# EEZ_AUX_PS_r5B6a.net
KiCad netlist of a schematic drawn in EAGLE
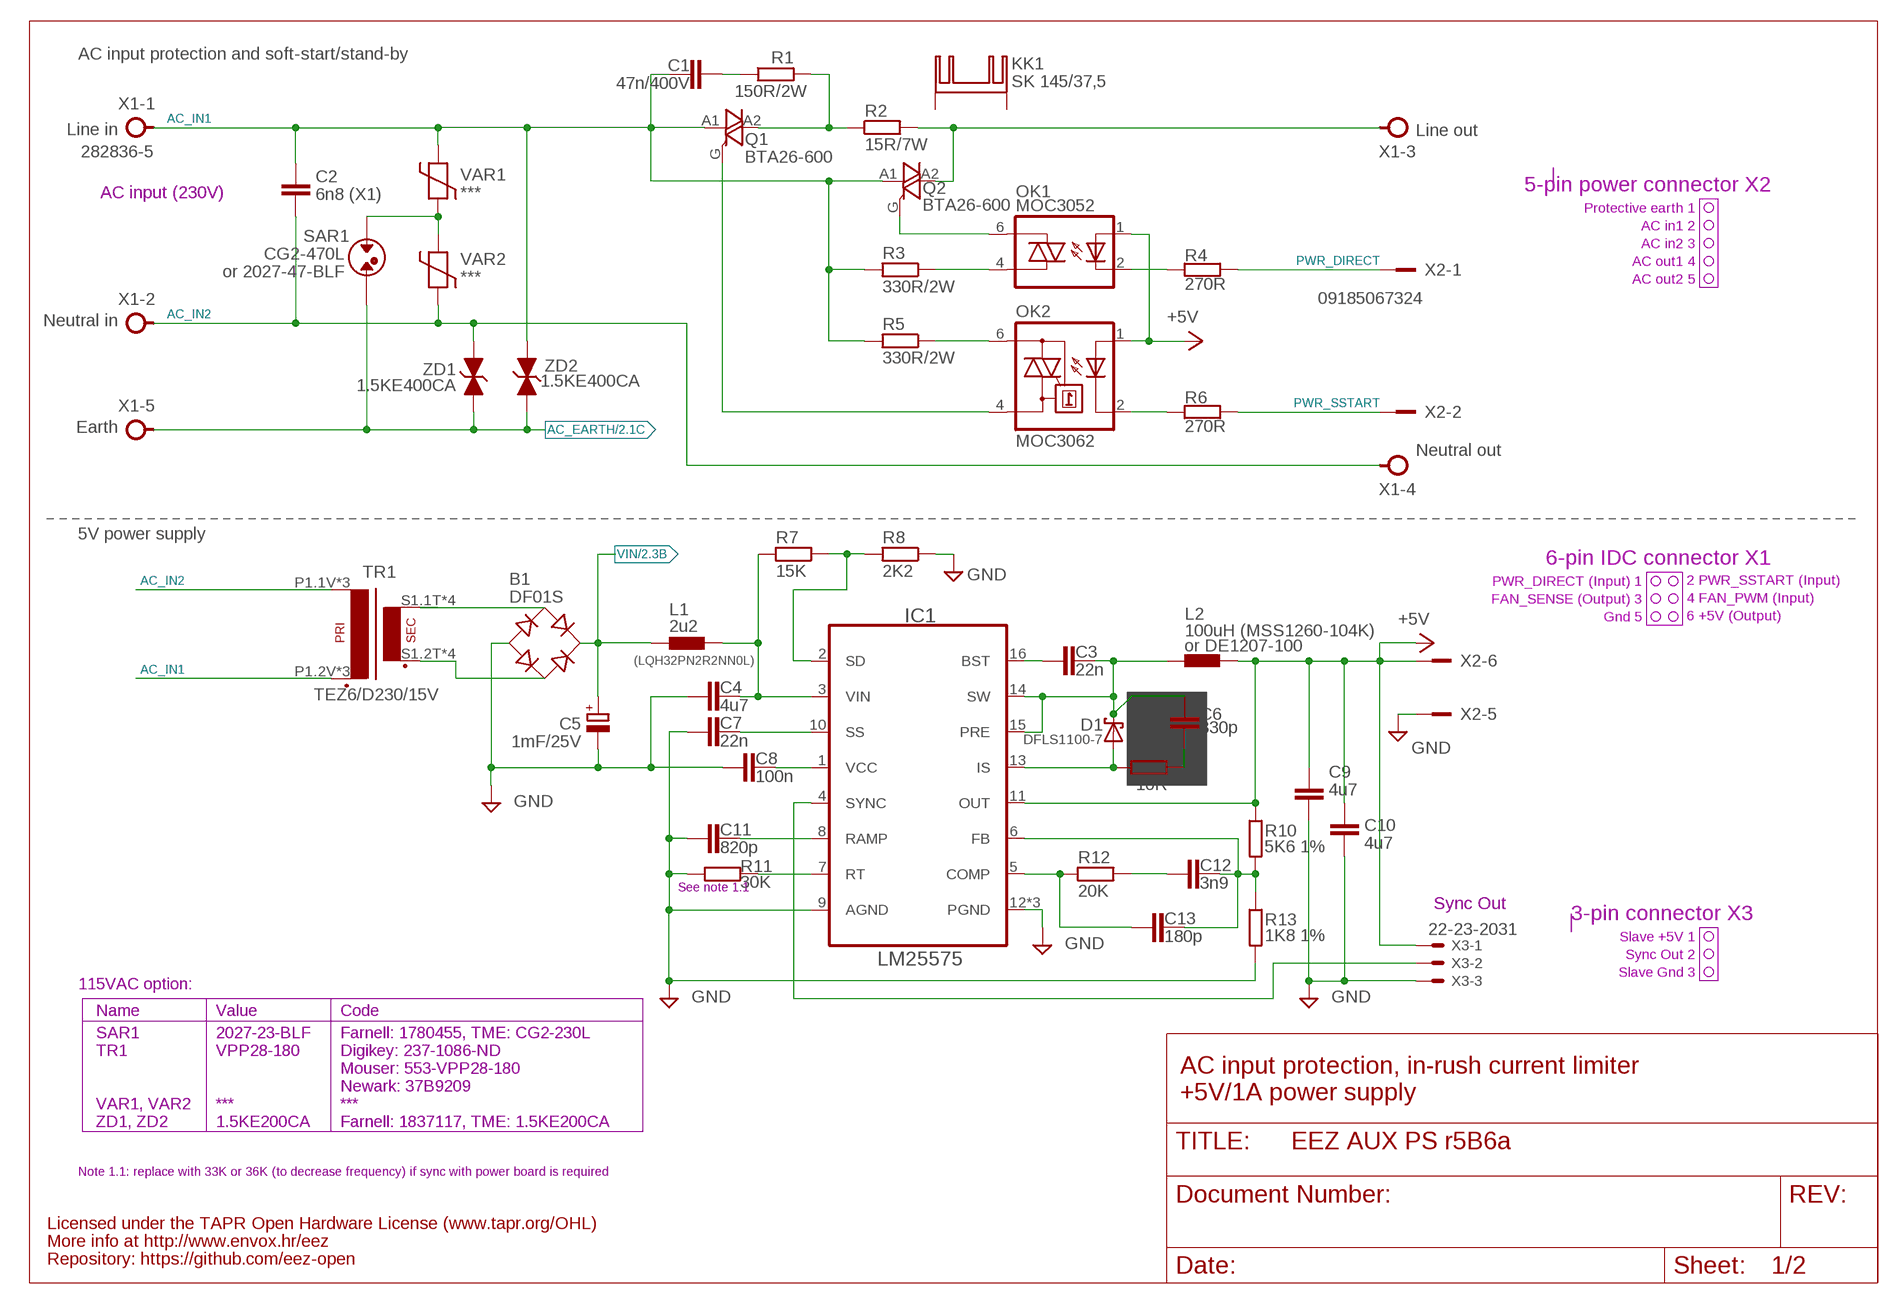
[diagram p0: schematic, sheet 1]
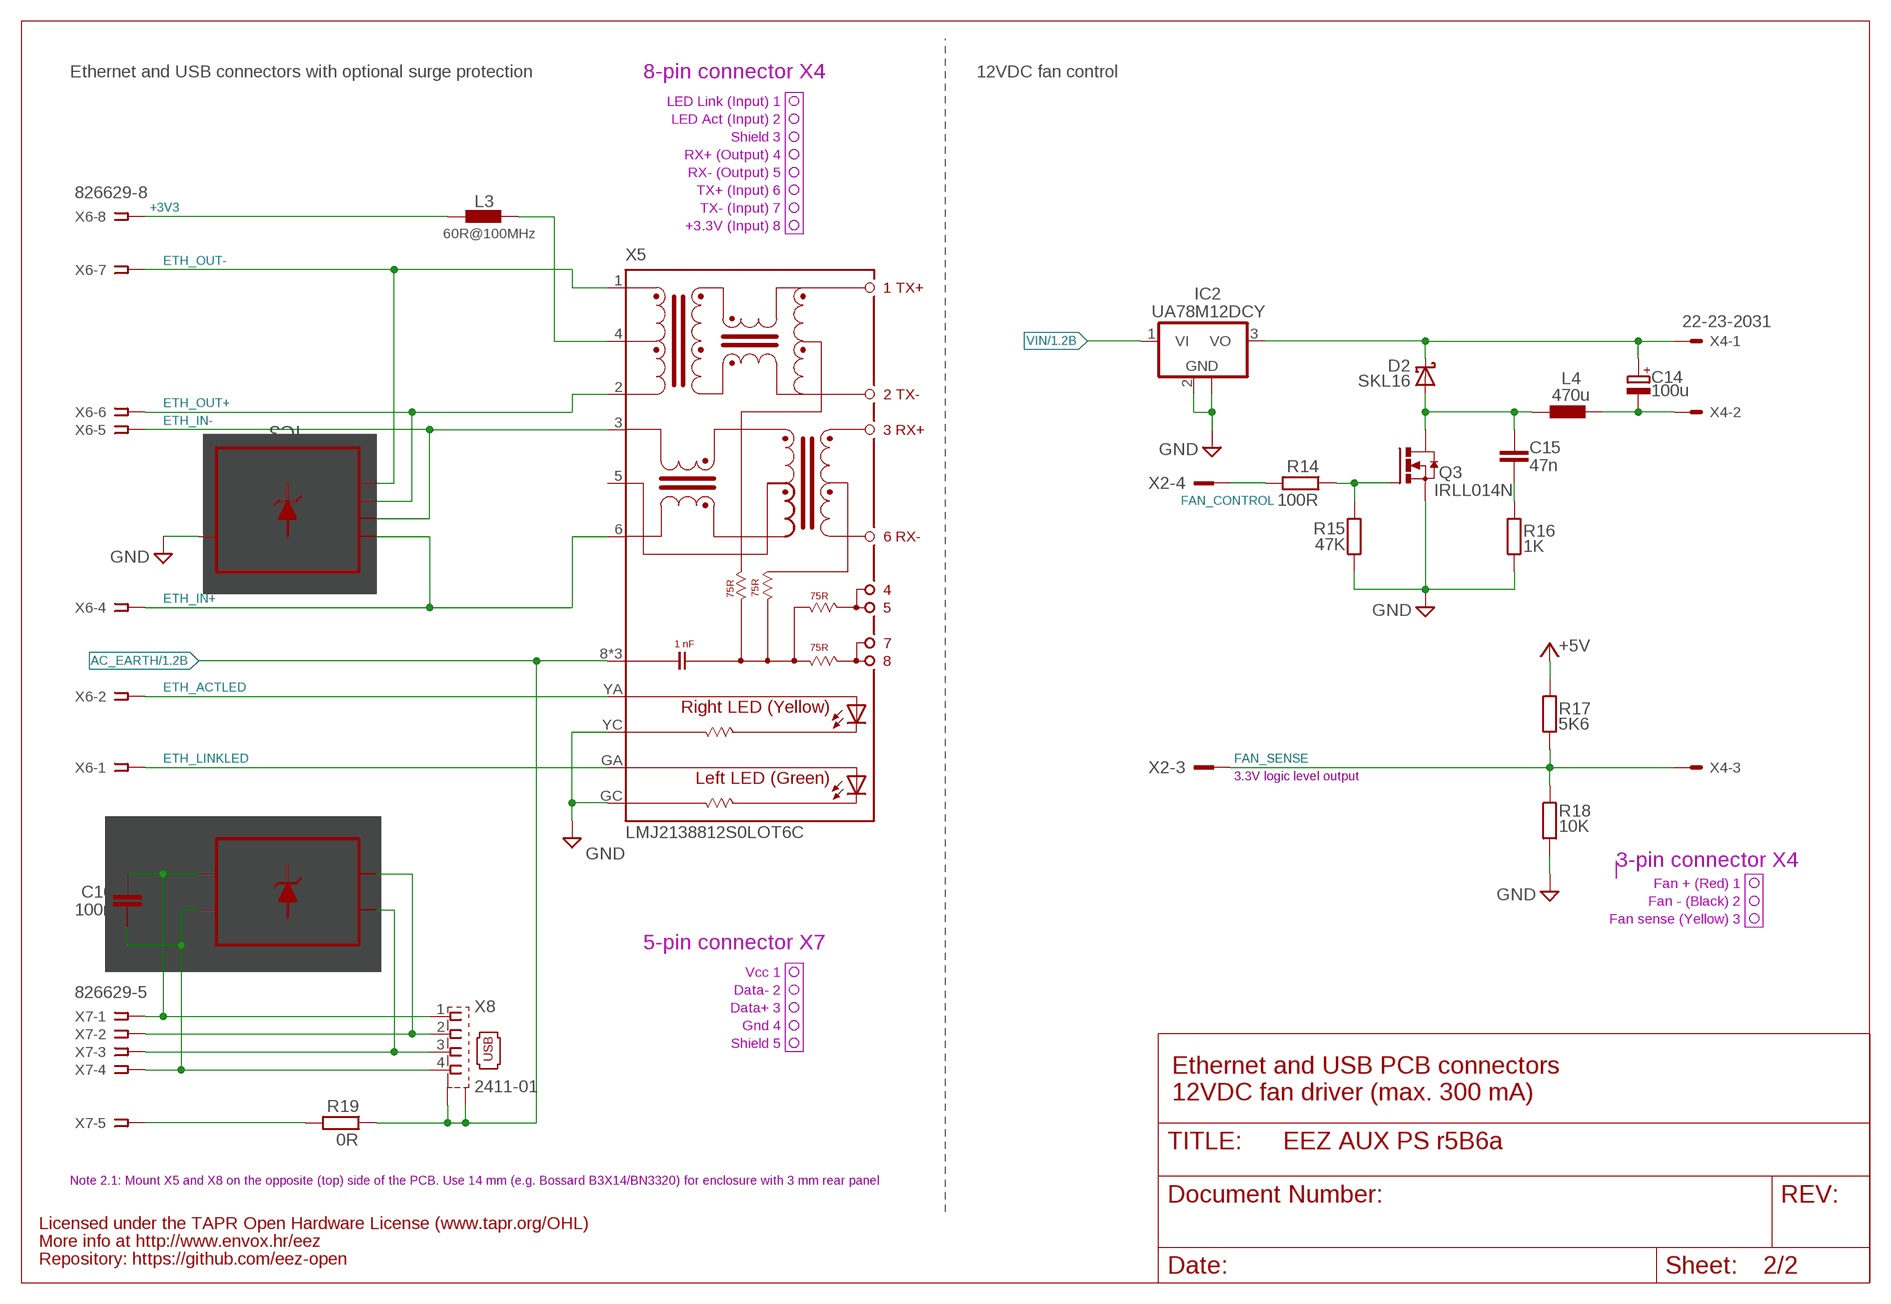
[diagram p1: schematic, sheet 2]

(export (version "E")
  (design (tool "Eeschema 10.0.6"))
  (components
    (comp (ref "B1")
      (value "DF01S")
      (footprint "eagle-import:DFS")
      (libsource (lib "eagle-import") (part "DFS01"))
    )
    (comp (ref "C1")
      (value "47n/400V")
      (footprint "eagle-import:C075-052X106")
      (libsource (lib "eagle-import") (part "C-EU075-052X106"))
    )
    (comp (ref "C2")
      (value "6n8 (X1)")
      (footprint "eagle-import:C102-064X133")
      (libsource (lib "eagle-import") (part "C-EU102-064X133"))
    )
    (comp (ref "C3")
      (value "22n")
      (footprint "eagle-import:C0805")
      (libsource (lib "eagle-import") (part "C-EUC0805"))
    )
    (comp (ref "C4")
      (value "4u7")
      (footprint "eagle-import:C1210")
      (libsource (lib "eagle-import") (part "C-EUC1210"))
    )
    (comp (ref "C5")
      (value "1mF/25V")
      (footprint "eagle-import:ECAP5_10.5")
      (libsource (lib "eagle-import") (part "ECAP5G_10.5MM"))
    )
    (comp (ref "C6")
      (value "330p")
      (footprint "eagle-import:C0805")
      (libsource (lib "eagle-import") (part "C-EUC0805"))
    )
    (comp (ref "C7")
      (value "22n")
      (footprint "eagle-import:C0805")
      (libsource (lib "eagle-import") (part "C-EUC0805"))
    )
    (comp (ref "C8")
      (value "100n")
      (footprint "eagle-import:C0805")
      (libsource (lib "eagle-import") (part "C-EUC0805"))
    )
    (comp (ref "C9")
      (value "4u7")
      (footprint "eagle-import:C1210")
      (libsource (lib "eagle-import") (part "C-EUC1210"))
    )
    (comp (ref "C10")
      (value "4u7")
      (footprint "eagle-import:C1210")
      (libsource (lib "eagle-import") (part "C-EUC1210"))
    )
    (comp (ref "C11")
      (value "820p")
      (footprint "eagle-import:C0805")
      (libsource (lib "eagle-import") (part "C-EUC0805"))
    )
    (comp (ref "C12")
      (value "3n9")
      (footprint "eagle-import:C0805")
      (libsource (lib "eagle-import") (part "C-EUC0805"))
    )
    (comp (ref "C13")
      (value "180p")
      (footprint "eagle-import:C0805")
      (libsource (lib "eagle-import") (part "C-EUC0805"))
    )
    (comp (ref "D1")
      (value "DFLS1100-7")
      (footprint "eagle-import:SOD123")
      (libsource (lib "eagle-import") (part "SCHOTTKYSOD123"))
    )
    (comp (ref "IC1")
      (value "LM25575")
      (footprint "eagle-import:SOP65P640X110-17N_HOLE")
      (libsource (lib "eagle-import") (part "LM(2)5575"))
    )
    (comp (ref "KK1")
      (value "SK 145/37,5")
      (footprint "eagle-import:SK145")
      (libsource (lib "eagle-import") (part "SK145"))
    )
    (comp (ref "L1")
      (value "2u2")
      (footprint "eagle-import:L1210")
      (libsource (lib "eagle-import") (part "L1210"))
    )
    (comp (ref "L2")
      (value "100uH (MSS1260-104K)")
      (footprint "eagle-import:MSS1278")
      (libsource (lib "eagle-import") (part "COILCRAFT_MSS1278"))
    )
    (comp (ref "OK1")
      (value "MOC3052")
      (footprint "eagle-import:DIL6-SMD")
      (libsource (lib "eagle-import") (part "MOC305X"))
    )
    (comp (ref "OK2")
      (value "MOC3062")
      (footprint "eagle-import:DIL6-SMD")
      (fields
        (field (name "MF") "FAIRCHILD SEMICONDUCTOR")
        (field (name "MPN") "MOC3033S-M")
        (field (name "MF_1") "FAIRCHILD SEMICONDUCTOR")
        (field (name "MPN_1") "MOC3033S-M")
        (field (name "OC_FARNELL") "unknown")
        (field (name "OC_NEWARK") "05C2878")
      )
      (libsource (lib "eagle-import") (part "MOC30S33"))
    )
    (comp (ref "Q1")
      (value "BTA26-600")
      (footprint "eagle-import:TOP3S-1")
      (libsource (lib "eagle-import") (part "BTA26-V"))
    )
    (comp (ref "Q2")
      (value "BTA26-600")
      (footprint "eagle-import:TOP3S-1")
      (libsource (lib "eagle-import") (part "BTA26-V"))
    )
    (comp (ref "R1")
      (value "150R/2W")
      (footprint "eagle-import:R2512")
      (libsource (lib "eagle-import") (part "R-EU_R2512"))
    )
    (comp (ref "R2")
      (value "15R/7W")
      (footprint "eagle-import:R_0913")
      (libsource (lib "eagle-import") (part "R_EU7W"))
    )
    (comp (ref "R3")
      (value "330R/2W")
      (footprint "eagle-import:R2512")
      (libsource (lib "eagle-import") (part "R-EU_R2512"))
    )
    (comp (ref "R4")
      (value "270R")
      (footprint "eagle-import:R0805")
      (libsource (lib "eagle-import") (part "R-EU_R0805"))
    )
    (comp (ref "R5")
      (value "330R/2W")
      (footprint "eagle-import:R2512")
      (libsource (lib "eagle-import") (part "R-EU_R2512"))
    )
    (comp (ref "R6")
      (value "270R")
      (footprint "eagle-import:R0805")
      (libsource (lib "eagle-import") (part "R-EU_R0805"))
    )
    (comp (ref "R7")
      (value "15K")
      (footprint "eagle-import:R0805")
      (libsource (lib "eagle-import") (part "R-EU_R0805"))
    )
    (comp (ref "R8")
      (value "2K2")
      (footprint "eagle-import:R0805")
      (libsource (lib "eagle-import") (part "R-EU_R0805"))
    )
    (comp (ref "R9")
      (value "10R")
      (footprint "eagle-import:R1206")
      (libsource (lib "eagle-import") (part "R-EU_R1206"))
    )
    (comp (ref "R10")
      (value "5K6 1%")
      (footprint "eagle-import:R0805")
      (libsource (lib "eagle-import") (part "R-EU_R0805"))
    )
    (comp (ref "R11")
      (value "30K")
      (footprint "eagle-import:R0805")
      (libsource (lib "eagle-import") (part "R-EU_R0805"))
    )
    (comp (ref "R12")
      (value "20K")
      (footprint "eagle-import:R0805")
      (libsource (lib "eagle-import") (part "R-EU_R0805"))
    )
    (comp (ref "R13")
      (value "1K8 1%")
      (footprint "eagle-import:R0805")
      (libsource (lib "eagle-import") (part "R-EU_R0805"))
    )
    (comp (ref "SAR1")
      (value "CG2-470L")
      (footprint "eagle-import:SAR")
      (libsource (lib "eagle-import") (part "SAR"))
    )
    (comp (ref "TR1")
      (value "TEZ6/D230/15V")
      (footprint "eagle-import:PCB_TRAFO6VA_TEZ+VPP")
      (libsource (lib "eagle-import") (part "PCB_TRAFO6VA_TEZ+VPP"))
    )
    (comp (ref "VAR1")
      (value "***")
      (footprint "eagle-import:VARISTOR")
      (libsource (lib "eagle-import") (part "VARISTOR"))
    )
    (comp (ref "VAR2")
      (value "***")
      (footprint "eagle-import:VARISTOR")
      (libsource (lib "eagle-import") (part "VARISTOR"))
    )
    (comp (ref "X1")
      (value "282836-5")
      (footprint "eagle-import:TBLOCK5.0_5")
      (libsource (lib "eagle-import") (part "TBLOCK5.0_5A"))
    )
    (comp (ref "X2")
      (value "09185067324")
      (footprint "eagle-import:IDC-6PIN")
      (libsource (lib "eagle-import") (part "IDC-6PIN"))
    )
    (comp (ref "X3")
      (value "22-23-2031")
      (footprint "eagle-import:22-23-2031")
      (fields (field (name "MF") "MOLEX"))
      (libsource (lib "eagle-import") (part "22-23-2031"))
    )
    (comp (ref "ZD1")
      (value "1.5KE400CA")
      (footprint "eagle-import:DO201-BIDIR")
      (libsource (lib "eagle-import") (part "1.5KE-BIDIR"))
    )
    (comp (ref "ZD2")
      (value "1.5KE400CA")
      (footprint "eagle-import:DO201-BIDIR")
      (libsource (lib "eagle-import") (part "1.5KE-BIDIR"))
    )
    (comp (ref "C14")
      (value "100u")
      (footprint "eagle-import:CAPAE660X610N")
      (libsource (lib "eagle-import") (part "ECAPPANASONIC_H"))
    )
    (comp (ref "C15")
      (value "47n")
      (footprint "eagle-import:C0805")
      (libsource (lib "eagle-import") (part "C-EUC0805"))
    )
    (comp (ref "C16")
      (value "100n")
      (footprint "eagle-import:C0805")
      (libsource (lib "eagle-import") (part "C-EUC0805"))
    )
    (comp (ref "D2")
      (value "SKL16")
      (footprint "eagle-import:SOD123")
      (libsource (lib "eagle-import") (part "SCHOTTKYSOD123"))
    )
    (comp (ref "IC2")
      (value "UA78M12DCY")
      (footprint "eagle-import:SOT230P700X180-4N")
      (libsource (lib "eagle-import") (part "UA78MDCY"))
    )
    (comp (ref "IC3")
      (value "TPD4E002DRLR")
      (footprint "eagle-import:SOT50P280X60-5N")
      (libsource (lib "eagle-import") (part "TPD4E002DRLR"))
    )
    (comp (ref "IC4")
      (value "TPD2E001DZDR")
      (footprint "eagle-import:SOP192P292X122-4N")
      (libsource (lib "eagle-import") (part "TPD2E001DZDR"))
    )
    (comp (ref "L3")
      (value "60R@100MHz")
      (footprint "eagle-import:BEAD0603")
      (libsource (lib "eagle-import") (part "FERRITE_BEAD0603"))
    )
    (comp (ref "L4")
      (value "470u")
      (footprint "eagle-import:DE0704")
      (libsource (lib "eagle-import") (part "DE0704"))
    )
    (comp (ref "Q3")
      (value "IRLL014N")
      (footprint "eagle-import:SOT223")
      (libsource (lib "eagle-import") (part "N-HEXFET-2D_?-SOT232IRLL014N"))
    )
    (comp (ref "R14")
      (value "100R")
      (footprint "eagle-import:R0805")
      (libsource (lib "eagle-import") (part "R-EU_R0805"))
    )
    (comp (ref "R15")
      (value "47K")
      (footprint "eagle-import:R0805")
      (libsource (lib "eagle-import") (part "R-EU_R0805"))
    )
    (comp (ref "R16")
      (value "1K")
      (footprint "eagle-import:R0805")
      (libsource (lib "eagle-import") (part "R-EU_R0805"))
    )
    (comp (ref "R17")
      (value "5K6")
      (footprint "eagle-import:R0805")
      (libsource (lib "eagle-import") (part "R-EU_R0805"))
    )
    (comp (ref "R18")
      (value "10K")
      (footprint "eagle-import:R0805")
      (libsource (lib "eagle-import") (part "R-EU_R0805"))
    )
    (comp (ref "R19")
      (value "0R")
      (footprint "eagle-import:R0805")
      (libsource (lib "eagle-import") (part "R-EU_R0805"))
    )
    (comp (ref "X4")
      (value "22-23-2031")
      (footprint "eagle-import:22-23-2031")
      (fields (field (name "MF") "MOLEX"))
      (libsource (lib "eagle-import") (part "22-23-2031"))
    )
    (comp (ref "X5")
      (value "LMJ2138812S0LOT6C")
      (footprint "eagle-import:RJ45-VERT")
      (libsource (lib "eagle-import") (part "RJ45-VERT"))
    )
    (comp (ref "X6")
      (value "826629-8")
      (footprint "eagle-import:SSW-108-02-S-S")
      (fields (field (name "MPN") "SSW-108-02-S-S"))
      (libsource (lib "eagle-import") (part "SSW-108-02-S-S"))
    )
    (comp (ref "X7")
      (value "826629-5")
      (footprint "eagle-import:SSW-105-02-S-S")
      (fields (field (name "MPN") "SSW-105-02-S-S"))
      (libsource (lib "eagle-import") (part "SSW-105-02-S-S"))
    )
    (comp (ref "X8")
      (value "2411-01")
      (footprint "eagle-import:KUSBVX-BS1N")
      (libsource (lib "eagle-import") (part "KUSBVX-BS1N"))
    )
  )
  (nets
    (net (code "1") (name "+3V3") (class "Default")
      (node (ref "L3") (pin "P$2") (pinfunction "2_P$2") (pintype "passive"))
      (node (ref "X6") (pin "8") (pinfunction "1_8") (pintype "passive"))
    )
    (net (code "2") (name "+5V") (class "Default")
      (node (ref "C10") (pin "1") (pinfunction "1_1") (pintype "passive"))
      (node (ref "C9") (pin "1") (pinfunction "1_1") (pintype "passive"))
      (node (ref "IC1") (pin "11") (pinfunction "OUT_11") (pintype "output"))
      (node (ref "L2") (pin "2") (pinfunction "2_2") (pintype "passive"))
      (node (ref "OK1") (pin "1") (pinfunction "A_1") (pintype "passive"))
      (node (ref "OK2") (pin "1") (pinfunction "A_1") (pintype "passive"))
      (node (ref "R10") (pin "1") (pinfunction "1_1") (pintype "passive"))
      (node (ref "R17") (pin "1") (pinfunction "1_1") (pintype "passive"))
      (node (ref "X2") (pin "6") (pinfunction "1_6") (pintype "passive"))
      (node (ref "X3") (pin "1") (pinfunction "S_1") (pintype "passive"))
    )
    (net (code "3") (name "AC_EARTH") (class "Default")
      (node (ref "R19") (pin "1") (pinfunction "1_1") (pintype "passive"))
      (node (ref "SAR1") (pin "P$2") (pinfunction "P$2_P$2") (pintype "bidirectional"))
      (node (ref "X1") (pin "5") (pinfunction "1_5") (pintype "bidirectional"))
      (node (ref "X5") (pin "8") (pinfunction "SH_8") (pintype "input"))
      (node (ref "X5") (pin "SH1") (pinfunction "SH_SH1") (pintype "input"))
      (node (ref "X5") (pin "SH2") (pinfunction "SH_SH2") (pintype "input"))
      (node (ref "X8") (pin "M1") (pinfunction "S1_M1") (pintype "passive"))
      (node (ref "X8") (pin "M2") (pinfunction "S2_M2") (pintype "passive"))
      (node (ref "ZD1") (pin "C") (pinfunction "1_C") (pintype "passive"))
      (node (ref "ZD2") (pin "C") (pinfunction "1_C") (pintype "passive"))
    )
    (net (code "4") (name "AC_IN1") (class "Default")
      (node (ref "C1") (pin "2") (pinfunction "2_2") (pintype "passive"))
      (node (ref "C2") (pin "1") (pinfunction "1_1") (pintype "passive"))
      (node (ref "Q1") (pin "A1") (pinfunction "A1_A1") (pintype "passive"))
      (node (ref "Q2") (pin "A1") (pinfunction "A1_A1") (pintype "passive"))
      (node (ref "R3") (pin "2") (pinfunction "2_2") (pintype "passive"))
      (node (ref "R5") (pin "2") (pinfunction "2_2") (pintype "passive"))
      (node (ref "TR1") (pin "P1.2V") (pinfunction "P2_P1.2V") (pintype "passive"))
      (node (ref "TR1") (pin "P2.2V") (pinfunction "P2_P2.2V") (pintype "passive"))
      (node (ref "TR1") (pin "P2_TEZ") (pinfunction "P2_P2_TEZ") (pintype "passive"))
      (node (ref "VAR1") (pin "P$2") (pinfunction "P$2_P$2") (pintype "bidirectional"))
      (node (ref "X1") (pin "1") (pinfunction "1_1") (pintype "bidirectional"))
      (node (ref "ZD2") (pin "A") (pinfunction "2_A") (pintype "passive"))
    )
    (net (code "5") (name "AC_IN2") (class "Default")
      (node (ref "C2") (pin "2") (pinfunction "2_2") (pintype "passive"))
      (node (ref "TR1") (pin "P1.1V") (pinfunction "P1_P1.1V") (pintype "passive"))
      (node (ref "TR1") (pin "P1_TEZ") (pinfunction "P1_P1_TEZ") (pintype "passive"))
      (node (ref "TR1") (pin "P2.1V") (pinfunction "P1_P2.1V") (pintype "passive"))
      (node (ref "VAR2") (pin "P$1") (pinfunction "P$1_P$1") (pintype "bidirectional"))
      (node (ref "X1") (pin "2") (pinfunction "1_2") (pintype "bidirectional"))
      (node (ref "X1") (pin "4") (pinfunction "1_4") (pintype "bidirectional"))
      (node (ref "ZD1") (pin "A") (pinfunction "2_A") (pintype "passive"))
    )
    (net (code "6") (name "ETH_ACTLED") (class "Default")
      (node (ref "X5") (pin "YA") (pinfunction "YELLOW_A_YA") (pintype "passive"))
      (node (ref "X6") (pin "2") (pinfunction "1_2") (pintype "passive"))
    )
    (net (code "7") (name "ETH_IN+") (class "Default")
      (node (ref "IC3") (pin "5") (pinfunction "IO4_5") (pintype "bidirectional"))
      (node (ref "X5") (pin "6") (pinfunction "RD-_6") (pintype "input"))
      (node (ref "X6") (pin "4") (pinfunction "1_4") (pintype "passive"))
    )
    (net (code "8") (name "ETH_IN-") (class "Default")
      (node (ref "IC3") (pin "4") (pinfunction "IO3_4") (pintype "bidirectional"))
      (node (ref "X5") (pin "3") (pinfunction "RD+_3") (pintype "input"))
      (node (ref "X6") (pin "5") (pinfunction "1_5") (pintype "passive"))
    )
    (net (code "9") (name "ETH_LINKLED") (class "Default")
      (node (ref "X5") (pin "GA") (pinfunction "GREEN-A_GA") (pintype "passive"))
      (node (ref "X6") (pin "1") (pinfunction "1_1") (pintype "passive"))
    )
    (net (code "10") (name "ETH_OUT+") (class "Default")
      (node (ref "IC3") (pin "3") (pinfunction "IO2_3") (pintype "bidirectional"))
      (node (ref "X5") (pin "2") (pinfunction "TD-_2") (pintype "input"))
      (node (ref "X6") (pin "6") (pinfunction "1_6") (pintype "passive"))
    )
    (net (code "11") (name "ETH_OUT-") (class "Default")
      (node (ref "IC3") (pin "1") (pinfunction "IO1_1") (pintype "bidirectional"))
      (node (ref "X5") (pin "1") (pinfunction "TD+_1") (pintype "input"))
      (node (ref "X6") (pin "7") (pinfunction "1_7") (pintype "passive"))
    )
    (net (code "12") (name "FAN_CONTROL") (class "Default")
      (node (ref "R14") (pin "2") (pinfunction "2_2") (pintype "passive"))
      (node (ref "X2") (pin "4") (pinfunction "1_4") (pintype "passive"))
    )
    (net (code "13") (name "FAN_SENSE") (class "Default")
      (node (ref "R17") (pin "2") (pinfunction "2_2") (pintype "passive"))
      (node (ref "R18") (pin "1") (pinfunction "1_1") (pintype "passive"))
      (node (ref "X2") (pin "3") (pinfunction "1_3") (pintype "passive"))
      (node (ref "X4") (pin "3") (pinfunction "S_3") (pintype "passive"))
    )
    (net (code "14") (name "GND") (class "Default")
      (node (ref "B1") (pin "-") (pinfunction "-_-") (pintype "passive"))
      (node (ref "C10") (pin "2") (pinfunction "2_2") (pintype "passive"))
      (node (ref "C11") (pin "1") (pinfunction "1_1") (pintype "passive"))
      (node (ref "C4") (pin "2") (pinfunction "2_2") (pintype "passive"))
      (node (ref "C5") (pin "-") (pinfunction "-_-") (pintype "passive"))
      (node (ref "C7") (pin "2") (pinfunction "2_2") (pintype "passive"))
      (node (ref "C8") (pin "1") (pinfunction "1_1") (pintype "passive"))
      (node (ref "C9") (pin "2") (pinfunction "2_2") (pintype "passive"))
      (node (ref "IC1") (pin "12") (pinfunction "PGND_12") (pintype "passive"))
      (node (ref "IC1") (pin "9") (pinfunction "AGND_9") (pintype "passive"))
      (node (ref "IC1") (pin "TP") (pinfunction "PGND_TP") (pintype "passive"))
      (node (ref "IC1") (pin "TP2") (pinfunction "PGND_TP2") (pintype "passive"))
      (node (ref "IC2") (pin "2") (pinfunction "GND_2") (pintype "passive"))
      (node (ref "IC2") (pin "4") (pinfunction "GND_4") (pintype "passive"))
      (node (ref "IC3") (pin "2") (pinfunction "GND_2") (pintype "passive"))
      (node (ref "Q3") (pin "3") (pinfunction "S_3") (pintype "passive"))
      (node (ref "R11") (pin "2") (pinfunction "2_2") (pintype "passive"))
      (node (ref "R13") (pin "2") (pinfunction "2_2") (pintype "passive"))
      (node (ref "R15") (pin "1") (pinfunction "1_1") (pintype "passive"))
      (node (ref "R16") (pin "1") (pinfunction "1_1") (pintype "passive"))
      (node (ref "R18") (pin "2") (pinfunction "2_2") (pintype "passive"))
      (node (ref "R8") (pin "1") (pinfunction "1_1") (pintype "passive"))
      (node (ref "X2") (pin "5") (pinfunction "1_5") (pintype "passive"))
      (node (ref "X3") (pin "3") (pinfunction "S_3") (pintype "passive"))
      (node (ref "X5") (pin "GC") (pinfunction "GREEN-C_GC") (pintype "passive"))
      (node (ref "X5") (pin "YC") (pinfunction "YELLOW-C_YC") (pintype "passive"))
    )
    (net (code "15") (name "Net-(B1-PadAC1)") (class "Default")
      (node (ref "B1") (pin "AC1") (pinfunction "AC1_AC1") (pintype "passive"))
      (node (ref "TR1") (pin "S1.1T") (pinfunction "S1_S1.1T") (pintype "passive"))
      (node (ref "TR1") (pin "S1.1V") (pinfunction "S1_S1.1V") (pintype "passive"))
      (node (ref "TR1") (pin "S2.1T") (pinfunction "S1_S2.1T") (pintype "passive"))
      (node (ref "TR1") (pin "S2.1V") (pinfunction "S1_S2.1V") (pintype "passive"))
    )
    (net (code "16") (name "Net-(B1-PadAC2)") (class "Default")
      (node (ref "B1") (pin "AC2") (pinfunction "AC2_AC2") (pintype "passive"))
      (node (ref "TR1") (pin "S1.2T") (pinfunction "S2_S1.2T") (pintype "passive"))
      (node (ref "TR1") (pin "S1.2V") (pinfunction "S2_S1.2V") (pintype "passive"))
      (node (ref "TR1") (pin "S2.2T") (pinfunction "S2_S2.2T") (pintype "passive"))
      (node (ref "TR1") (pin "S2.2V") (pinfunction "S2_S2.2V") (pintype "passive"))
    )
    (net (code "17") (name "Net-(C1-Pad1)") (class "Default")
      (node (ref "C1") (pin "1") (pinfunction "1_1") (pintype "passive"))
      (node (ref "R1") (pin "1") (pinfunction "1_1") (pintype "passive"))
    )
    (net (code "18") (name "Net-(C6-Pad2)") (class "Default")
      (node (ref "C6") (pin "2") (pinfunction "2_2") (pintype "passive"))
      (node (ref "R9") (pin "2") (pinfunction "2_2") (pintype "passive"))
    )
    (net (code "19") (name "Net-(C12-Pad2)") (class "Default")
      (node (ref "C12") (pin "2") (pinfunction "2_2") (pintype "passive"))
      (node (ref "R12") (pin "2") (pinfunction "2_2") (pintype "passive"))
    )
    (net (code "20") (name "Net-(C14-+)") (class "Default")
      (node (ref "C14") (pin "1") (pinfunction "+_1") (pintype "passive"))
      (node (ref "D2") (pin "C") (pinfunction "C_C") (pintype "passive"))
      (node (ref "IC2") (pin "3") (pinfunction "VO_3") (pintype "passive"))
      (node (ref "X4") (pin "1") (pinfunction "S_1") (pintype "passive"))
    )
    (net (code "21") (name "Net-(C14--)") (class "Default")
      (node (ref "C14") (pin "2") (pinfunction "-_2") (pintype "passive"))
      (node (ref "L4") (pin "1") (pinfunction "1_1") (pintype "passive"))
      (node (ref "X4") (pin "2") (pinfunction "S_2") (pintype "passive"))
    )
    (net (code "22") (name "Net-(C15-Pad1)") (class "Default")
      (node (ref "C15") (pin "1") (pinfunction "1_1") (pintype "passive"))
      (node (ref "R16") (pin "2") (pinfunction "2_2") (pintype "passive"))
    )
    (net (code "23") (name "Net-(C15-Pad2)") (class "Default")
      (node (ref "C15") (pin "2") (pinfunction "2_2") (pintype "passive"))
      (node (ref "D2") (pin "A") (pinfunction "A_A") (pintype "passive"))
      (node (ref "L4") (pin "2") (pinfunction "2_2") (pintype "passive"))
      (node (ref "Q3") (pin "2") (pinfunction "D_2") (pintype "passive"))
      (node (ref "Q3") (pin "4") (pinfunction "D_4") (pintype "passive"))
    )
    (net (code "24") (name "Net-(IC1-BST)") (class "Default")
      (node (ref "C3") (pin "2") (pinfunction "2_2") (pintype "passive"))
      (node (ref "IC1") (pin "16") (pinfunction "BST_16") (pintype "input"))
    )
    (net (code "25") (name "Net-(IC1-COMP)") (class "Default")
      (node (ref "C13") (pin "2") (pinfunction "2_2") (pintype "passive"))
      (node (ref "IC1") (pin "5") (pinfunction "COMP_5") (pintype "input"))
      (node (ref "R12") (pin "1") (pinfunction "1_1") (pintype "passive"))
    )
    (net (code "26") (name "Net-(IC1-FB)") (class "Default")
      (node (ref "C12") (pin "1") (pinfunction "1_1") (pintype "passive"))
      (node (ref "C13") (pin "1") (pinfunction "1_1") (pintype "passive"))
      (node (ref "IC1") (pin "6") (pinfunction "FB_6") (pintype "input"))
      (node (ref "R10") (pin "2") (pinfunction "2_2") (pintype "passive"))
      (node (ref "R13") (pin "1") (pinfunction "1_1") (pintype "passive"))
    )
    (net (code "27") (name "Net-(IC1-IS)") (class "Default")
      (node (ref "D1") (pin "A") (pinfunction "A_A") (pintype "passive"))
      (node (ref "IC1") (pin "13") (pinfunction "IS_13") (pintype "input"))
      (node (ref "R9") (pin "1") (pinfunction "1_1") (pintype "passive"))
    )
    (net (code "28") (name "Net-(IC1-PRE)") (class "Default")
      (node (ref "C3") (pin "1") (pinfunction "1_1") (pintype "passive"))
      (node (ref "C6") (pin "1") (pinfunction "1_1") (pintype "passive"))
      (node (ref "D1") (pin "C") (pinfunction "C_C") (pintype "passive"))
      (node (ref "IC1") (pin "14") (pinfunction "SW_14") (pintype "output"))
      (node (ref "IC1") (pin "15") (pinfunction "PRE_15") (pintype "input"))
      (node (ref "L2") (pin "1") (pinfunction "1_1") (pintype "passive"))
    )
    (net (code "29") (name "Net-(IC1-RAMP)") (class "Default")
      (node (ref "C11") (pin "2") (pinfunction "2_2") (pintype "passive"))
      (node (ref "IC1") (pin "8") (pinfunction "RAMP_8") (pintype "input"))
    )
    (net (code "30") (name "Net-(IC1-RT)") (class "Default")
      (node (ref "IC1") (pin "7") (pinfunction "RT_7") (pintype "input"))
      (node (ref "R11") (pin "1") (pinfunction "1_1") (pintype "passive"))
    )
    (net (code "31") (name "Net-(IC1-SD)") (class "Default")
      (node (ref "IC1") (pin "2") (pinfunction "SD_2") (pintype "input"))
      (node (ref "R7") (pin "1") (pinfunction "1_1") (pintype "passive"))
      (node (ref "R8") (pin "2") (pinfunction "2_2") (pintype "passive"))
    )
    (net (code "32") (name "Net-(IC1-SS)") (class "Default")
      (node (ref "C7") (pin "1") (pinfunction "1_1") (pintype "passive"))
      (node (ref "IC1") (pin "10") (pinfunction "SS_10") (pintype "input"))
    )
    (net (code "33") (name "Net-(IC1-SYNC)") (class "Default")
      (node (ref "IC1") (pin "4") (pinfunction "SYNC_4") (pintype "input"))
      (node (ref "X3") (pin "2") (pinfunction "S_2") (pintype "passive"))
    )
    (net (code "34") (name "Net-(IC1-VCC)") (class "Default")
      (node (ref "C8") (pin "2") (pinfunction "2_2") (pintype "passive"))
      (node (ref "IC1") (pin "1") (pinfunction "VCC_1") (pintype "power_in"))
    )
    (net (code "35") (name "Net-(IC1-VIN)") (class "Default")
      (node (ref "C4") (pin "1") (pinfunction "1_1") (pintype "passive"))
      (node (ref "IC1") (pin "3") (pinfunction "VIN_3") (pintype "input"))
      (node (ref "L1") (pin "2") (pinfunction "2_2") (pintype "passive"))
      (node (ref "R7") (pin "2") (pinfunction "2_2") (pintype "passive"))
    )
    (net (code "36") (name "Net-(IC4-GND)") (class "Default")
      (node (ref "C16") (pin "1") (pinfunction "1_1") (pintype "passive"))
      (node (ref "IC4") (pin "1") (pinfunction "GND_1") (pintype "passive"))
      (node (ref "X7") (pin "4") (pinfunction "1_4") (pintype "passive"))
      (node (ref "X8") (pin "4") (pinfunction "4_4") (pintype "passive"))
    )
    (net (code "37") (name "Net-(IC4-IO1)") (class "Default")
      (node (ref "IC4") (pin "2") (pinfunction "IO1_2") (pintype "bidirectional"))
      (node (ref "X7") (pin "2") (pinfunction "1_2") (pintype "passive"))
      (node (ref "X8") (pin "2") (pinfunction "2_2") (pintype "passive"))
    )
    (net (code "38") (name "Net-(IC4-IO2)") (class "Default")
      (node (ref "IC4") (pin "3") (pinfunction "IO2_3") (pintype "bidirectional"))
      (node (ref "X7") (pin "3") (pinfunction "1_3") (pintype "passive"))
      (node (ref "X8") (pin "3") (pinfunction "3_3") (pintype "passive"))
    )
    (net (code "39") (name "Net-(IC4-VCC)") (class "Default")
      (node (ref "C16") (pin "2") (pinfunction "2_2") (pintype "passive"))
      (node (ref "IC4") (pin "4") (pinfunction "VCC_4") (pintype "power_in"))
      (node (ref "X7") (pin "1") (pinfunction "1_1") (pintype "passive"))
      (node (ref "X8") (pin "1") (pinfunction "1_1") (pintype "passive"))
    )
    (net (code "40") (name "Net-(L3-1)") (class "Default")
      (node (ref "L3") (pin "P$1") (pinfunction "1_P$1") (pintype "passive"))
      (node (ref "X5") (pin "4") (pinfunction "CT_4") (pintype "input"))
    )
    (net (code "41") (name "Net-(OK1-A1)") (class "Default")
      (node (ref "OK1") (pin "4") (pinfunction "A1_4") (pintype "passive"))
      (node (ref "R3") (pin "1") (pinfunction "1_1") (pintype "passive"))
    )
    (net (code "42") (name "Net-(OK1-A2)") (class "Default")
      (node (ref "OK1") (pin "6") (pinfunction "A2_6") (pintype "passive"))
      (node (ref "Q2") (pin "G") (pinfunction "G_G") (pintype "passive"))
    )
    (net (code "43") (name "Net-(OK1-C)") (class "Default")
      (node (ref "OK1") (pin "2") (pinfunction "C_2") (pintype "passive"))
      (node (ref "R4") (pin "1") (pinfunction "1_1") (pintype "passive"))
    )
    (net (code "44") (name "Net-(OK2-A1)") (class "Default")
      (node (ref "OK2") (pin "4") (pinfunction "A1_4") (pintype "passive"))
      (node (ref "Q1") (pin "G") (pinfunction "G_G") (pintype "passive"))
    )
    (net (code "45") (name "Net-(OK2-A2)") (class "Default")
      (node (ref "OK2") (pin "6") (pinfunction "A2_6") (pintype "passive"))
      (node (ref "R5") (pin "1") (pinfunction "1_1") (pintype "passive"))
    )
    (net (code "46") (name "Net-(OK2-C)") (class "Default")
      (node (ref "OK2") (pin "2") (pinfunction "C_2") (pintype "passive"))
      (node (ref "R6") (pin "1") (pinfunction "1_1") (pintype "passive"))
    )
    (net (code "47") (name "Net-(Q1-PadA2)") (class "Default")
      (node (ref "Q1") (pin "A2") (pinfunction "A2_A2") (pintype "passive"))
      (node (ref "R1") (pin "2") (pinfunction "2_2") (pintype "passive"))
      (node (ref "R2") (pin "1") (pinfunction "1_1") (pintype "passive"))
    )
    (net (code "48") (name "Net-(Q3-G)") (class "Default")
      (node (ref "Q3") (pin "1") (pinfunction "G_1") (pintype "passive"))
      (node (ref "R14") (pin "1") (pinfunction "1_1") (pintype "passive"))
      (node (ref "R15") (pin "2") (pinfunction "2_2") (pintype "passive"))
    )
    (net (code "49") (name "Net-(SAR1-PadP$1)") (class "Default")
      (node (ref "SAR1") (pin "P$1") (pinfunction "P$1_P$1") (pintype "bidirectional"))
      (node (ref "VAR1") (pin "P$1") (pinfunction "P$1_P$1") (pintype "bidirectional"))
      (node (ref "VAR2") (pin "P$2") (pinfunction "P$2_P$2") (pintype "bidirectional"))
    )
    (net (code "50") (name "Net-(X1C-1)") (class "Default")
      (node (ref "Q2") (pin "A2") (pinfunction "A2_A2") (pintype "passive"))
      (node (ref "R2") (pin "2") (pinfunction "2_2") (pintype "passive"))
      (node (ref "X1") (pin "3") (pinfunction "1_3") (pintype "bidirectional"))
    )
    (net (code "51") (name "Net-(X7E-1)") (class "Default")
      (node (ref "R19") (pin "2") (pinfunction "2_2") (pintype "passive"))
      (node (ref "X7") (pin "5") (pinfunction "1_5") (pintype "passive"))
    )
    (net (code "52") (name "PWR_DIRECT") (class "Default")
      (node (ref "R4") (pin "2") (pinfunction "2_2") (pintype "passive"))
      (node (ref "X2") (pin "1") (pinfunction "1_1") (pintype "passive"))
    )
    (net (code "53") (name "PWR_SSTART") (class "Default")
      (node (ref "R6") (pin "2") (pinfunction "2_2") (pintype "passive"))
      (node (ref "X2") (pin "2") (pinfunction "1_2") (pintype "passive"))
    )
    (net (code "54") (name "VIN") (class "Default")
      (node (ref "B1") (pin "+") (pinfunction "+_+") (pintype "passive"))
      (node (ref "C5") (pin "+") (pinfunction "+_+") (pintype "passive"))
      (node (ref "IC2") (pin "1") (pinfunction "VI_1") (pintype "input"))
      (node (ref "L1") (pin "1") (pinfunction "1_1") (pintype "passive"))
    )
    (net (code "55") (name "unconnected-(KK1-K-Pad1)") (class "Default")
      (node (ref "KK1") (pin "1") (pinfunction "K_1") (pintype "passive"))
    )
    (net (code "56") (name "unconnected-(KK1-K-Pad2)") (class "Default")
      (node (ref "KK1") (pin "2") (pinfunction "K_2") (pintype "passive"))
    )
    (net (code "57") (name "unconnected-(X5-CR-Pad5)") (class "Default")
      (node (ref "X5") (pin "5") (pinfunction "CR_5") (pintype "input"))
    )
  )
)
